# attiny45-musicbox.net
KiCad netlist of a schematic drawn in EAGLE
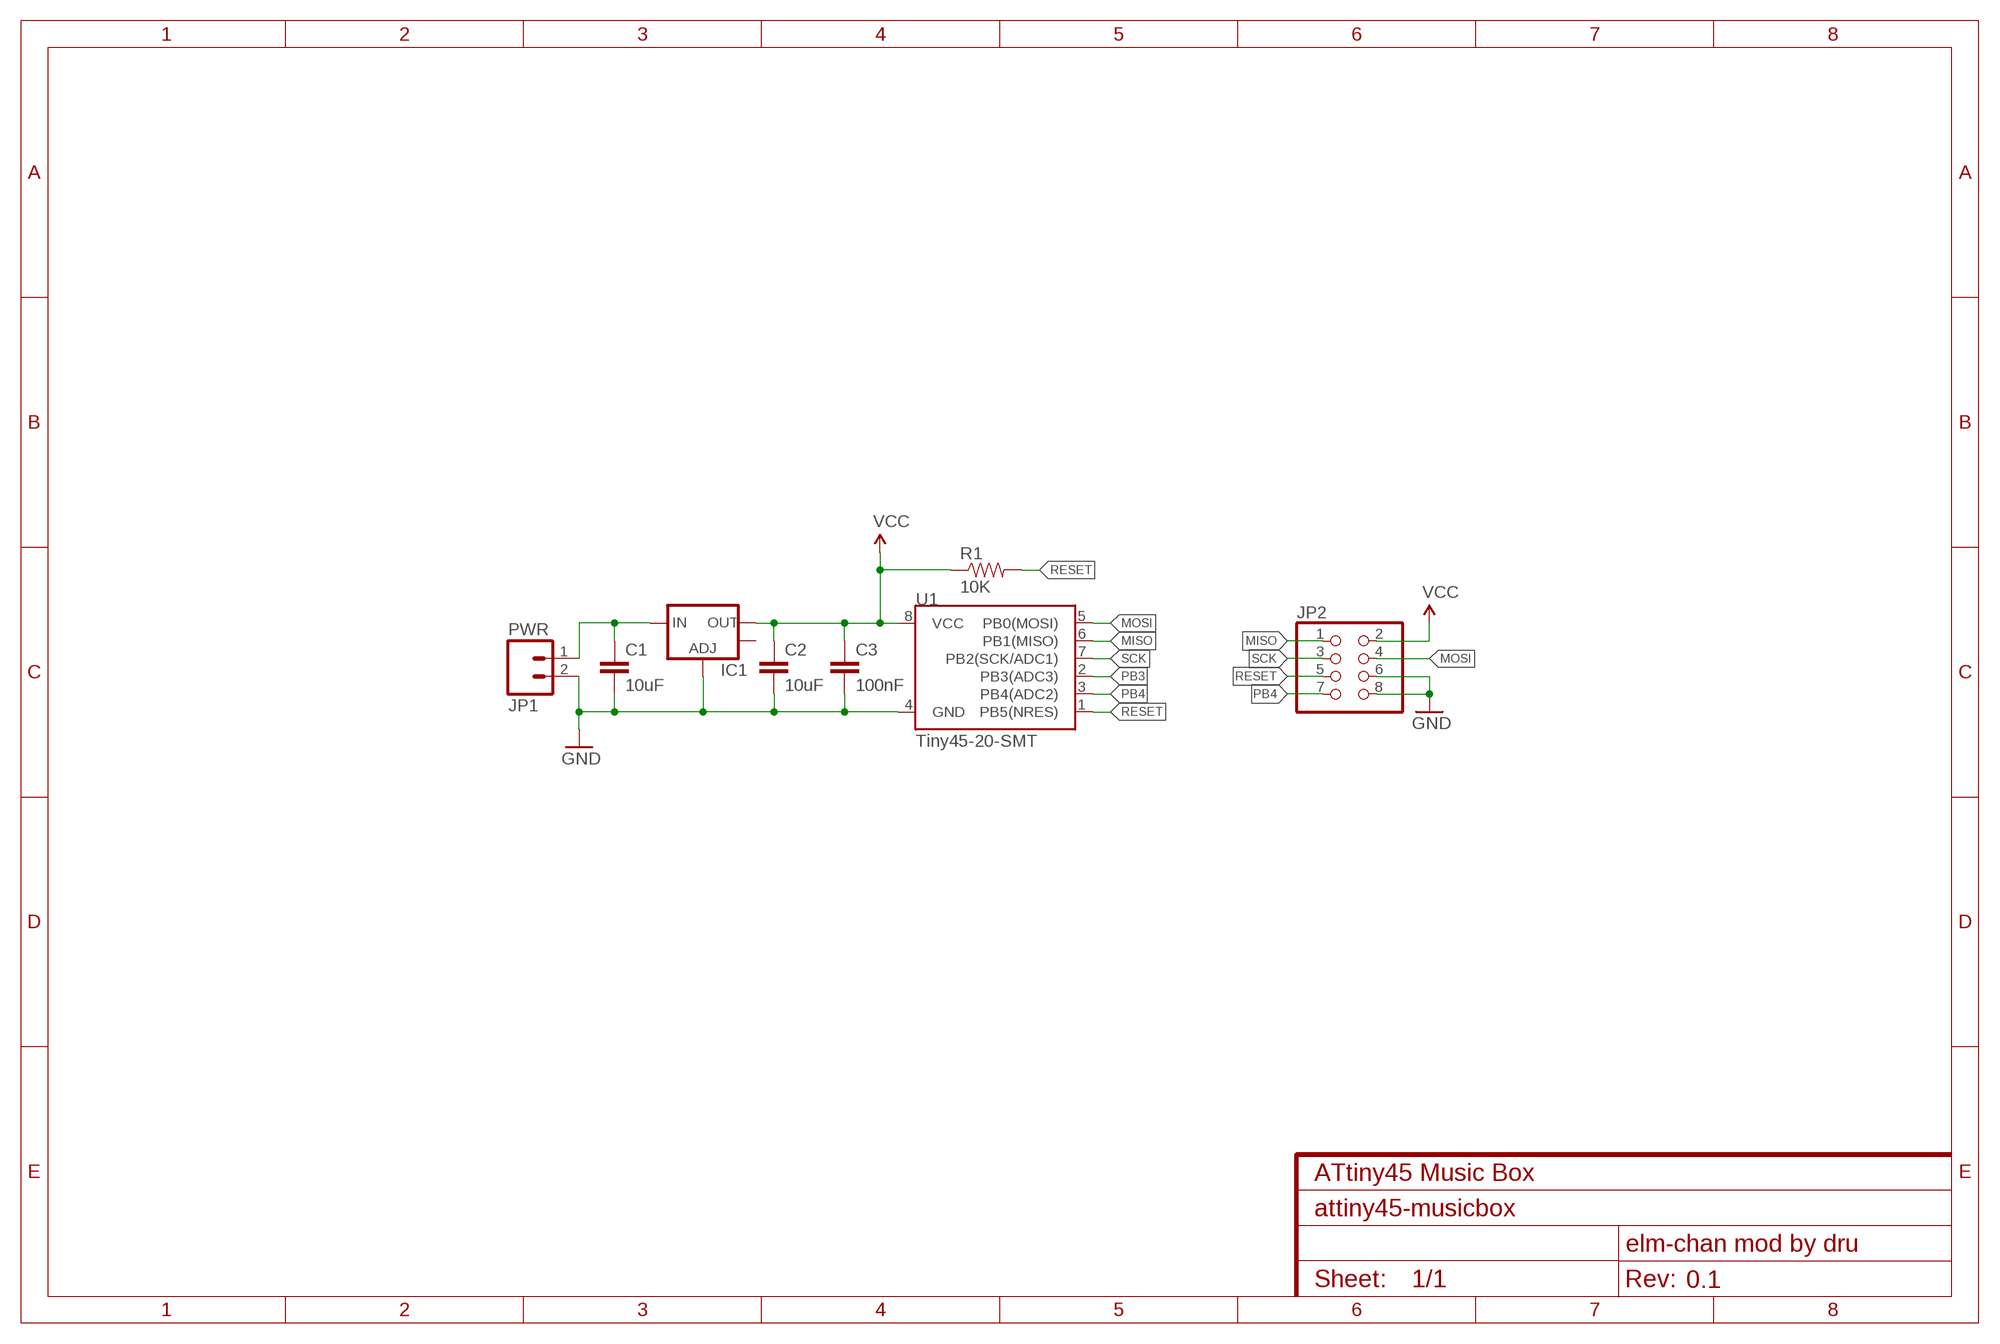
[diagram p0: schematic, sheet 1]

(export (version "E")
  (design (tool "Eeschema 10.0.6"))
  (components
    (comp (ref "C1")
      (value "10uF")
      (footprint "eagle-import:0805")
      (libsource (lib "eagle-import") (part "CAP0805"))
    )
    (comp (ref "C2")
      (value "10uF")
      (footprint "eagle-import:0805")
      (libsource (lib "eagle-import") (part "CAP0805"))
    )
    (comp (ref "C3")
      (value "100nF")
      (footprint "eagle-import:0805")
      (libsource (lib "eagle-import") (part "CAP0805"))
    )
    (comp (ref "IC1")
      (value "V_REG_LM1117SOT223")
      (footprint "eagle-import:SOT223")
      (libsource (lib "eagle-import") (part "V_REG_LM1117SOT223"))
    )
    (comp (ref "JP1")
      (value "PWR")
      (footprint "eagle-import:1X02")
      (libsource (lib "eagle-import") (part "M02PTH"))
    )
    (comp (ref "JP2")
      (value "PINHD-2X4")
      (footprint "eagle-import:2X04")
      (libsource (lib "eagle-import") (part "PINHD-2X4"))
    )
    (comp (ref "R1")
      (value "10K")
      (footprint "eagle-import:0603-RES")
      (libsource (lib "eagle-import") (part "RESISTOR0603-RES"))
    )
    (comp (ref "U1")
      (value "Tiny45-20-SMT")
      (footprint "eagle-import:SO08-EIAJ")
      (libsource (lib "eagle-import") (part "ATTINY45TINY45-20-SMT"))
    )
  )
  (nets
    (net (code "1") (name "GND") (class "Default")
      (node (ref "C1") (pin "2") (pinfunction "2_2") (pintype "passive"))
      (node (ref "C2") (pin "2") (pinfunction "2_2") (pintype "passive"))
      (node (ref "C3") (pin "2") (pinfunction "2_2") (pintype "passive"))
      (node (ref "IC1") (pin "1") (pinfunction "ADJ_1") (pintype "input"))
      (node (ref "JP1") (pin "2") (pinfunction "2_2") (pintype "passive"))
      (node (ref "JP2") (pin "6") (pinfunction "6_6") (pintype "passive"))
      (node (ref "JP2") (pin "8") (pinfunction "8_8") (pintype "passive"))
      (node (ref "U1") (pin "4") (pinfunction "GND_4") (pintype "bidirectional"))
    )
    (net (code "2") (name "MISO") (class "Default")
      (node (ref "JP2") (pin "1") (pinfunction "1_1") (pintype "passive"))
      (node (ref "U1") (pin "6") (pinfunction "PB1(MISO)_6") (pintype "bidirectional"))
    )
    (net (code "3") (name "MOSI") (class "Default")
      (node (ref "JP2") (pin "4") (pinfunction "4_4") (pintype "passive"))
      (node (ref "U1") (pin "5") (pinfunction "PB0(MOSI)_5") (pintype "bidirectional"))
    )
    (net (code "4") (name "Net-(IC1-IN)") (class "Default")
      (node (ref "C1") (pin "1") (pinfunction "1_1") (pintype "passive"))
      (node (ref "IC1") (pin "3") (pinfunction "IN_3") (pintype "input"))
      (node (ref "JP1") (pin "1") (pinfunction "1_1") (pintype "passive"))
    )
    (net (code "5") (name "PB3") (class "Default")
      (node (ref "U1") (pin "2") (pinfunction "PB3(ADC3)_2") (pintype "bidirectional"))
    )
    (net (code "6") (name "PB4") (class "Default")
      (node (ref "JP2") (pin "7") (pinfunction "7_7") (pintype "passive"))
      (node (ref "U1") (pin "3") (pinfunction "PB4(ADC2)_3") (pintype "bidirectional"))
    )
    (net (code "7") (name "RESET") (class "Default")
      (node (ref "JP2") (pin "5") (pinfunction "5_5") (pintype "passive"))
      (node (ref "R1") (pin "2") (pinfunction "2_2") (pintype "passive"))
      (node (ref "U1") (pin "1") (pinfunction "PB5(NRES)_1") (pintype "bidirectional"))
    )
    (net (code "8") (name "SCK") (class "Default")
      (node (ref "JP2") (pin "3") (pinfunction "3_3") (pintype "passive"))
      (node (ref "U1") (pin "7") (pinfunction "PB2(SCK/ADC1)_7") (pintype "bidirectional"))
    )
    (net (code "9") (name "VCC") (class "Default")
      (node (ref "C2") (pin "1") (pinfunction "1_1") (pintype "passive"))
      (node (ref "C3") (pin "1") (pinfunction "1_1") (pintype "passive"))
      (node (ref "IC1") (pin "2") (pinfunction "OUT_2") (pintype "output"))
      (node (ref "JP2") (pin "2") (pinfunction "2_2") (pintype "passive"))
      (node (ref "R1") (pin "1") (pinfunction "1_1") (pintype "passive"))
      (node (ref "U1") (pin "8") (pinfunction "VCC_8") (pintype "bidirectional"))
    )
    (net (code "10") (name "unconnected-(IC1-OUT-Pad4)") (class "Default")
      (node (ref "IC1") (pin "4") (pinfunction "OUT_4") (pintype "output"))
    )
  )
)
